# 06_MIPI_CSI_Camera.net
KiCad netlist of a schematic drawn in Altium Designer
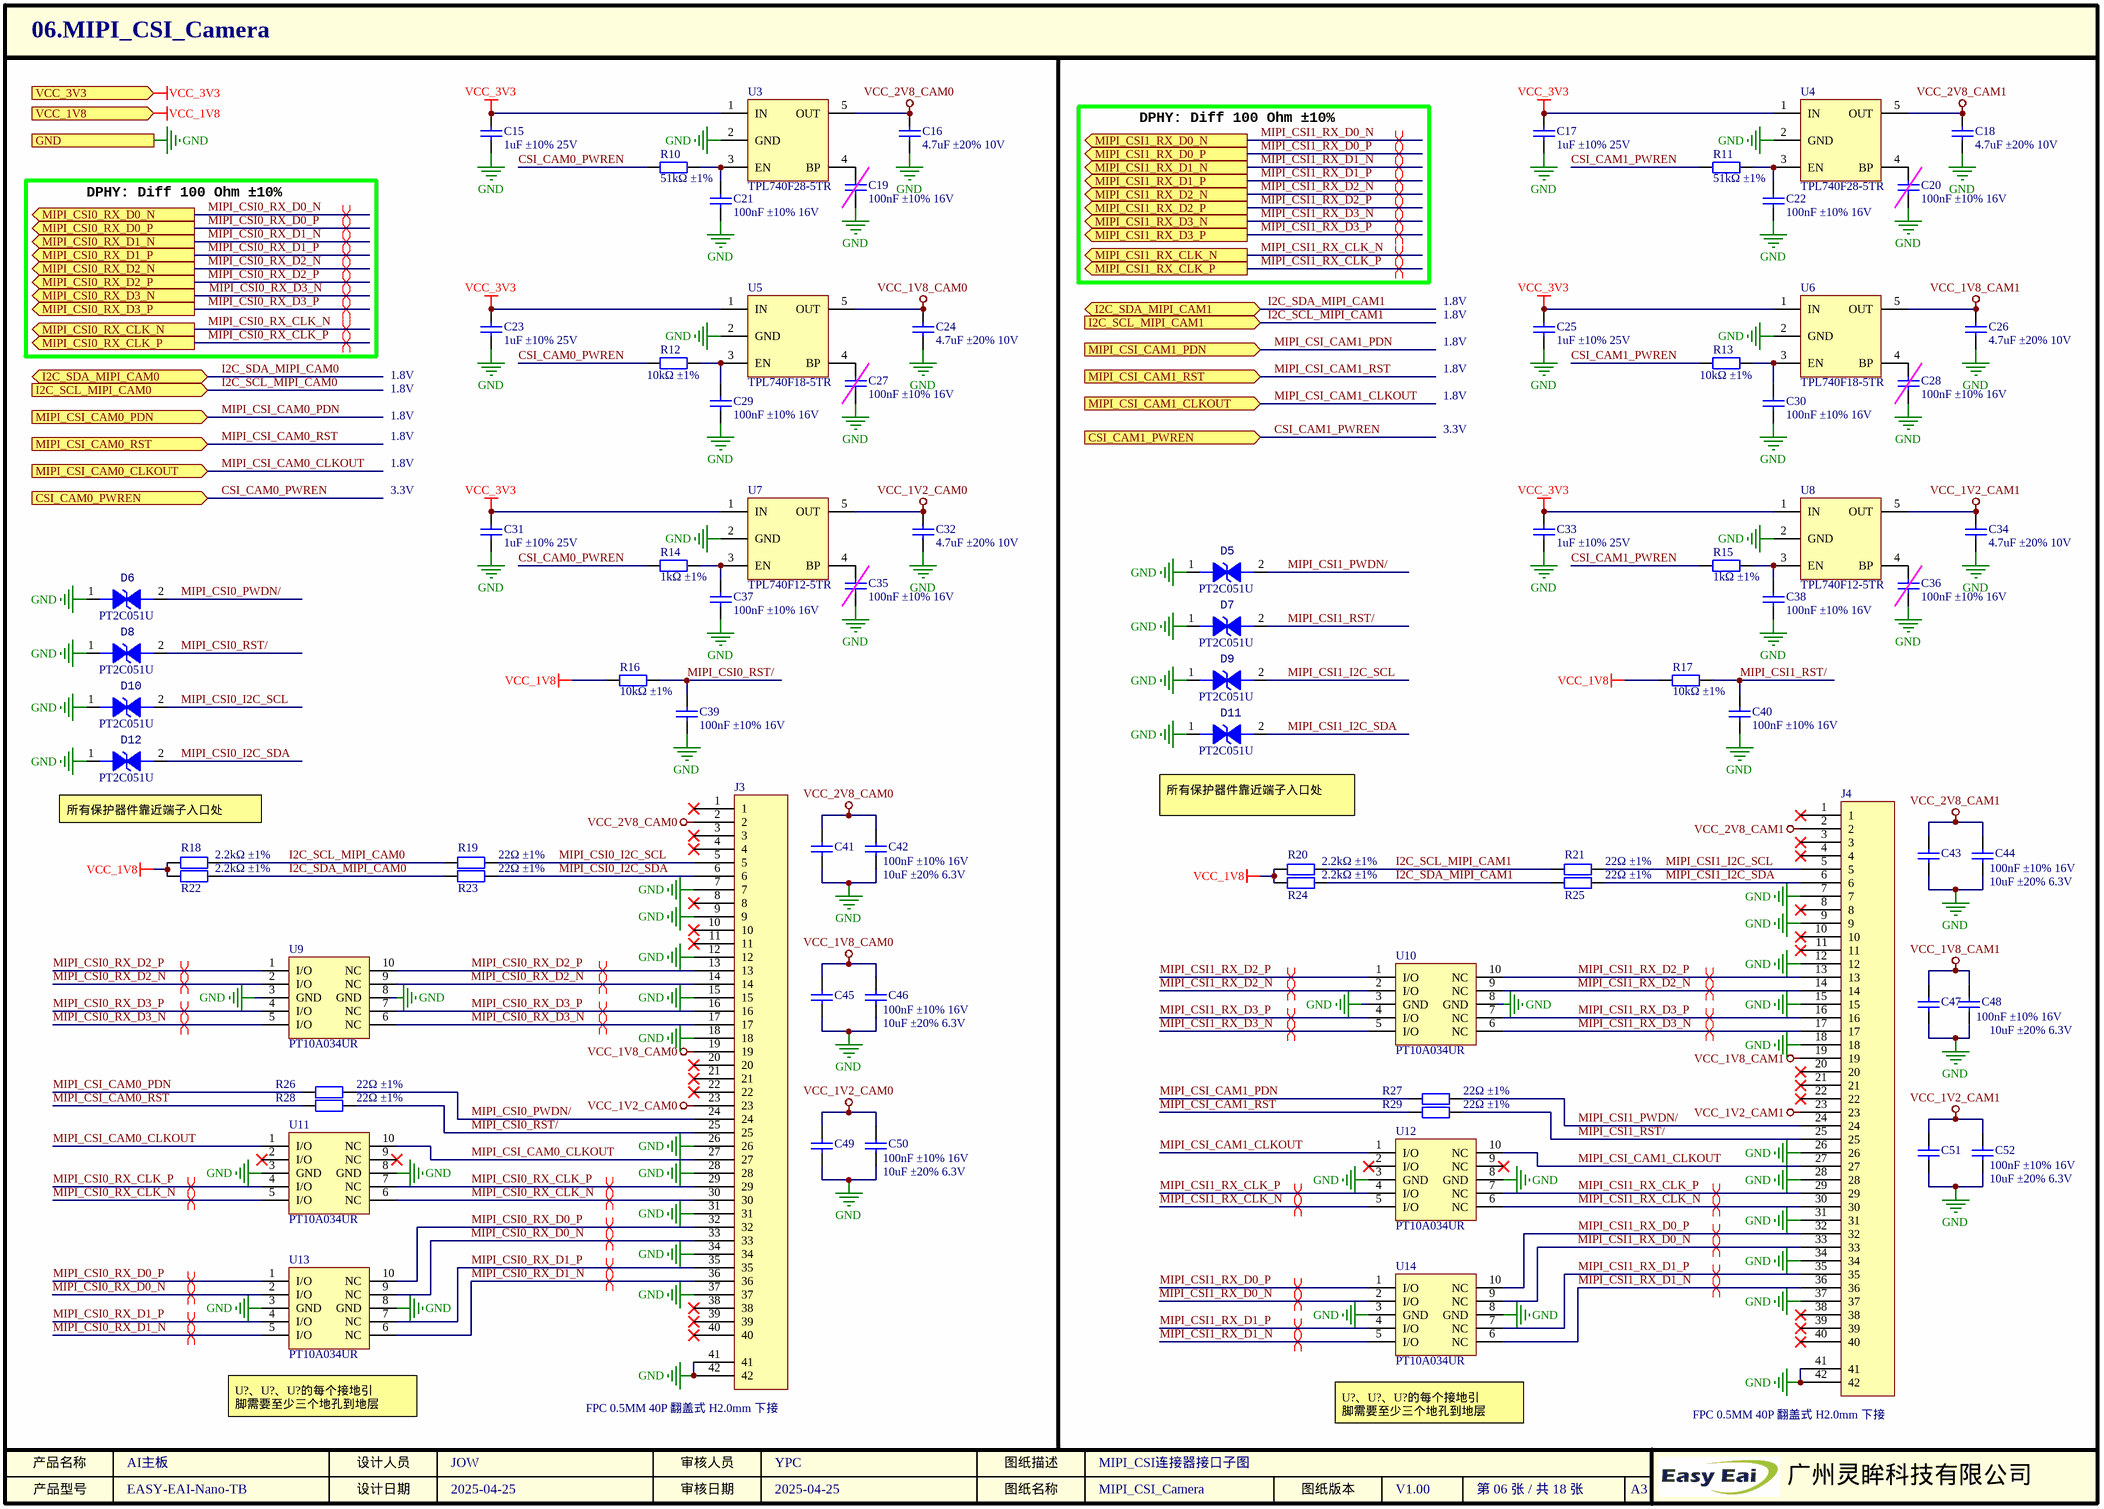
[diagram p0: 06.MIPI_CSI_Camera.SchDoc]

(export (version "E")
  (design (tool "Eeschema 10.0.6"))
  (components
    (comp (ref "C15")
      (value "CL05A105KA5NQNC")
      (footprint "0402_C")
      (description "SPZL000337")
      (fields (field (name "描述") "1uF ±10% 25V"))
      (libsource (lib "altium-import") (part "root_1_0402 1uF ±10% 25V_"))
    )
    (comp (ref "C16")
      (value "CL05A475MP5NRNC")
      (footprint "0402_C")
      (description "SPZL000339")
      (fields (field (name "描述") "4.7uF ±20% 10V"))
      (libsource (lib "altium-import") (part "root_1_0402 4.7uF ±20% 10V_"))
    )
    (comp (ref "C17")
      (value "CL05A105KA5NQNC")
      (footprint "0402_C")
      (description "SPZL000337")
      (fields (field (name "描述") "1uF ±10% 25V"))
      (libsource (lib "altium-import") (part "root_1_0402 1uF ±10% 25V_"))
    )
    (comp (ref "C18")
      (value "CL05A475MP5NRNC")
      (footprint "0402_C")
      (description "SPZL000339")
      (fields (field (name "描述") "4.7uF ±20% 10V"))
      (libsource (lib "altium-import") (part "root_1_0402 4.7uF ±20% 10V_"))
    )
    (comp (ref "C19")
      (value "CL05B104KO5NNNC")
      (footprint "0402_C")
      (description "SPZL000259")
      (fields (field (name "描述") "100nF ±10% 16V"))
      (libsource (lib "altium-import") (part "root_1_0402 100nF ±10% 16V_"))
    )
    (comp (ref "C20")
      (value "CL05B104KO5NNNC")
      (footprint "0402_C")
      (description "SPZL000259")
      (fields (field (name "描述") "100nF ±10% 16V"))
      (libsource (lib "altium-import") (part "root_1_0402 100nF ±10% 16V_"))
    )
    (comp (ref "C21")
      (value "CL05B104KO5NNNC")
      (footprint "0402_C")
      (description "SPZL000259")
      (fields (field (name "描述") "100nF ±10% 16V"))
      (libsource (lib "altium-import") (part "root_1_0402 100nF ±10% 16V_"))
    )
    (comp (ref "C22")
      (value "CL05B104KO5NNNC")
      (footprint "0402_C")
      (description "SPZL000259")
      (fields (field (name "描述") "100nF ±10% 16V"))
      (libsource (lib "altium-import") (part "root_1_0402 100nF ±10% 16V_"))
    )
    (comp (ref "C23")
      (value "CL05A105KA5NQNC")
      (footprint "0402_C")
      (description "SPZL000337")
      (fields (field (name "描述") "1uF ±10% 25V"))
      (libsource (lib "altium-import") (part "root_1_0402 1uF ±10% 25V_"))
    )
    (comp (ref "C24")
      (value "CL05A475MP5NRNC")
      (footprint "0402_C")
      (description "SPZL000339")
      (fields (field (name "描述") "4.7uF ±20% 10V"))
      (libsource (lib "altium-import") (part "root_1_0402 4.7uF ±20% 10V_"))
    )
    (comp (ref "C25")
      (value "CL05A105KA5NQNC")
      (footprint "0402_C")
      (description "SPZL000337")
      (fields (field (name "描述") "1uF ±10% 25V"))
      (libsource (lib "altium-import") (part "root_1_0402 1uF ±10% 25V_"))
    )
    (comp (ref "C26")
      (value "CL05A475MP5NRNC")
      (footprint "0402_C")
      (description "SPZL000339")
      (fields (field (name "描述") "4.7uF ±20% 10V"))
      (libsource (lib "altium-import") (part "root_1_0402 4.7uF ±20% 10V_"))
    )
    (comp (ref "C27")
      (value "CL05B104KO5NNNC")
      (footprint "0402_C")
      (description "SPZL000259")
      (fields (field (name "描述") "100nF ±10% 16V"))
      (libsource (lib "altium-import") (part "root_1_0402 100nF ±10% 16V_"))
    )
    (comp (ref "C28")
      (value "CL05B104KO5NNNC")
      (footprint "0402_C")
      (description "SPZL000259")
      (fields (field (name "描述") "100nF ±10% 16V"))
      (libsource (lib "altium-import") (part "root_1_0402 100nF ±10% 16V_"))
    )
    (comp (ref "C29")
      (value "CL05B104KO5NNNC")
      (footprint "0402_C")
      (description "SPZL000259")
      (fields (field (name "描述") "100nF ±10% 16V"))
      (libsource (lib "altium-import") (part "root_1_0402 100nF ±10% 16V_"))
    )
    (comp (ref "C30")
      (value "CL05B104KO5NNNC")
      (footprint "0402_C")
      (description "SPZL000259")
      (fields (field (name "描述") "100nF ±10% 16V"))
      (libsource (lib "altium-import") (part "root_1_0402 100nF ±10% 16V_"))
    )
    (comp (ref "C31")
      (value "CL05A105KA5NQNC")
      (footprint "0402_C")
      (description "SPZL000337")
      (fields (field (name "描述") "1uF ±10% 25V"))
      (libsource (lib "altium-import") (part "root_1_0402 1uF ±10% 25V_"))
    )
    (comp (ref "C32")
      (value "CL05A475MP5NRNC")
      (footprint "0402_C")
      (description "SPZL000339")
      (fields (field (name "描述") "4.7uF ±20% 10V"))
      (libsource (lib "altium-import") (part "root_1_0402 4.7uF ±20% 10V_"))
    )
    (comp (ref "C33")
      (value "CL05A105KA5NQNC")
      (footprint "0402_C")
      (description "SPZL000337")
      (fields (field (name "描述") "1uF ±10% 25V"))
      (libsource (lib "altium-import") (part "root_1_0402 1uF ±10% 25V_"))
    )
    (comp (ref "C34")
      (value "CL05A475MP5NRNC")
      (footprint "0402_C")
      (description "SPZL000339")
      (fields (field (name "描述") "4.7uF ±20% 10V"))
      (libsource (lib "altium-import") (part "root_1_0402 4.7uF ±20% 10V_"))
    )
    (comp (ref "C35")
      (value "CL05B104KO5NNNC")
      (footprint "0402_C")
      (description "SPZL000259")
      (fields (field (name "描述") "100nF ±10% 16V"))
      (libsource (lib "altium-import") (part "root_1_0402 100nF ±10% 16V_"))
    )
    (comp (ref "C36")
      (value "CL05B104KO5NNNC")
      (footprint "0402_C")
      (description "SPZL000259")
      (fields (field (name "描述") "100nF ±10% 16V"))
      (libsource (lib "altium-import") (part "root_1_0402 100nF ±10% 16V_"))
    )
    (comp (ref "C37")
      (value "CL05B104KO5NNNC")
      (footprint "0402_C")
      (description "SPZL000259")
      (fields (field (name "描述") "100nF ±10% 16V"))
      (libsource (lib "altium-import") (part "root_1_0402 100nF ±10% 16V_"))
    )
    (comp (ref "C38")
      (value "CL05B104KO5NNNC")
      (footprint "0402_C")
      (description "SPZL000259")
      (fields (field (name "描述") "100nF ±10% 16V"))
      (libsource (lib "altium-import") (part "root_1_0402 100nF ±10% 16V_"))
    )
    (comp (ref "C39")
      (value "CL05B104KO5NNNC")
      (footprint "0402_C")
      (description "SPZL000259")
      (fields (field (name "描述") "100nF ±10% 16V"))
      (libsource (lib "altium-import") (part "root_1_0402 100nF ±10% 16V_"))
    )
    (comp (ref "C40")
      (value "CL05B104KO5NNNC")
      (footprint "0402_C")
      (description "SPZL000259")
      (fields (field (name "描述") "100nF ±10% 16V"))
      (libsource (lib "altium-import") (part "root_1_0402 100nF ±10% 16V_"))
    )
    (comp (ref "C41")
      (value "CL05A106MQ5NUNC")
      (footprint "0402_C")
      (description "SPZL000269")
      (fields (field (name "描述") "10uF ±20% 6.3V"))
      (libsource (lib "altium-import") (part "root_1_0402 10uF ±20% 6.3V_"))
    )
    (comp (ref "C42")
      (value "CL05B104KO5NNNC")
      (footprint "0402_C")
      (description "SPZL000259")
      (fields (field (name "描述") "100nF ±10% 16V"))
      (libsource (lib "altium-import") (part "root_1_0402 100nF ±10% 16V_"))
    )
    (comp (ref "C43")
      (value "CL05A106MQ5NUNC")
      (footprint "0402_C")
      (description "SPZL000269")
      (fields (field (name "描述") "10uF ±20% 6.3V"))
      (libsource (lib "altium-import") (part "root_1_0402 10uF ±20% 6.3V_"))
    )
    (comp (ref "C44")
      (value "CL05B104KO5NNNC")
      (footprint "0402_C")
      (description "SPZL000259")
      (fields (field (name "描述") "100nF ±10% 16V"))
      (libsource (lib "altium-import") (part "root_1_0402 100nF ±10% 16V_"))
    )
    (comp (ref "C45")
      (value "CL05A106MQ5NUNC")
      (footprint "0402_C")
      (description "SPZL000269")
      (fields (field (name "描述") "10uF ±20% 6.3V"))
      (libsource (lib "altium-import") (part "root_1_0402 10uF ±20% 6.3V_"))
    )
    (comp (ref "C46")
      (value "CL05B104KO5NNNC")
      (footprint "0402_C")
      (description "SPZL000259")
      (fields (field (name "描述") "100nF ±10% 16V"))
      (libsource (lib "altium-import") (part "root_1_0402 100nF ±10% 16V_"))
    )
    (comp (ref "C47")
      (value "CL05A106MQ5NUNC")
      (footprint "0402_C")
      (description "SPZL000269")
      (fields (field (name "描述") "10uF ±20% 6.3V"))
      (libsource (lib "altium-import") (part "root_1_0402 10uF ±20% 6.3V_"))
    )
    (comp (ref "C48")
      (value "CL05B104KO5NNNC")
      (footprint "0402_C")
      (description "SPZL000259")
      (fields (field (name "描述") "100nF ±10% 16V"))
      (libsource (lib "altium-import") (part "root_1_0402 100nF ±10% 16V_"))
    )
    (comp (ref "C49")
      (value "CL05A106MQ5NUNC")
      (footprint "0402_C")
      (description "SPZL000269")
      (fields (field (name "描述") "10uF ±20% 6.3V"))
      (libsource (lib "altium-import") (part "root_1_0402 10uF ±20% 6.3V_"))
    )
    (comp (ref "C50")
      (value "CL05B104KO5NNNC")
      (footprint "0402_C")
      (description "SPZL000259")
      (fields (field (name "描述") "100nF ±10% 16V"))
      (libsource (lib "altium-import") (part "root_1_0402 100nF ±10% 16V_"))
    )
    (comp (ref "C51")
      (value "CL05A106MQ5NUNC")
      (footprint "0402_C")
      (description "SPZL000269")
      (fields (field (name "描述") "10uF ±20% 6.3V"))
      (libsource (lib "altium-import") (part "root_1_0402 10uF ±20% 6.3V_"))
    )
    (comp (ref "C52")
      (value "CL05B104KO5NNNC")
      (footprint "0402_C")
      (description "SPZL000259")
      (fields (field (name "描述") "100nF ±10% 16V"))
      (libsource (lib "altium-import") (part "root_1_0402 100nF ±10% 16V_"))
    )
    (comp (ref "D5")
      (value "PT2C051U")
      (footprint "DFN1006")
      (description "SPZL001147")
      (fields (field (name "型号") "PT2C051U"))
      (libsource (lib "ESD_EASY-EAI") (part "PT2C051U"))
    )
    (comp (ref "D6")
      (value "PT2C051U")
      (footprint "DFN1006")
      (description "SPZL001147")
      (fields (field (name "型号") "PT2C051U"))
      (libsource (lib "ESD_EASY-EAI") (part "PT2C051U"))
    )
    (comp (ref "D7")
      (value "PT2C051U")
      (footprint "DFN1006")
      (description "SPZL001147")
      (fields (field (name "型号") "PT2C051U"))
      (libsource (lib "ESD_EASY-EAI") (part "PT2C051U"))
    )
    (comp (ref "D8")
      (value "PT2C051U")
      (footprint "DFN1006")
      (description "SPZL001147")
      (fields (field (name "型号") "PT2C051U"))
      (libsource (lib "ESD_EASY-EAI") (part "PT2C051U"))
    )
    (comp (ref "D9")
      (value "PT2C051U")
      (footprint "DFN1006")
      (description "SPZL001147")
      (fields (field (name "型号") "PT2C051U"))
      (libsource (lib "ESD_EASY-EAI") (part "PT2C051U"))
    )
    (comp (ref "D10")
      (value "PT2C051U")
      (footprint "DFN1006")
      (description "SPZL001147")
      (fields (field (name "型号") "PT2C051U"))
      (libsource (lib "ESD_EASY-EAI") (part "PT2C051U"))
    )
    (comp (ref "D11")
      (value "PT2C051U")
      (footprint "DFN1006")
      (description "SPZL001147")
      (fields (field (name "型号") "PT2C051U"))
      (libsource (lib "ESD_EASY-EAI") (part "PT2C051U"))
    )
    (comp (ref "D12")
      (value "PT2C051U")
      (footprint "DFN1006")
      (description "SPZL001147")
      (fields (field (name "型号") "PT2C051U"))
      (libsource (lib "ESD_EASY-EAI") (part "PT2C051U"))
    )
    (comp (ref "J3")
      (value "AFC01-S40FCA-00")
      (footprint "FFC0.5-40P")
      (description "SPZL000107")
      (fields (field (name "描述") "FPC 0.5MM 40P 翻盖式 H2.0mm 下接"))
      (libsource (lib "FPC_EASY-EAI") (part "FPC 0.5MM 40P 翻盖式 H2.0mm 下接"))
    )
    (comp (ref "J4")
      (value "AFC01-S40FCA-00")
      (footprint "FFC0.5-40P")
      (description "SPZL000107")
      (fields (field (name "描述") "FPC 0.5MM 40P 翻盖式 H2.0mm 下接"))
      (libsource (lib "FPC_EASY-EAI") (part "FPC 0.5MM 40P 翻盖式 H2.0mm 下接"))
    )
    (comp (ref "R10")
      (value "0402WGF5102TCE")
      (footprint "0402_R")
      (description "SPZL000788")
      (fields (field (name "描述") "51kΩ ±1%"))
      (libsource (lib "RES_EASY-EAI") (part "0402 51kΩ ±1%"))
    )
    (comp (ref "R11")
      (value "0402WGF5102TCE")
      (footprint "0402_R")
      (description "SPZL000788")
      (fields (field (name "描述") "51kΩ ±1%"))
      (libsource (lib "RES_EASY-EAI") (part "0402 51kΩ ±1%"))
    )
    (comp (ref "R12")
      (value "0402WGF1002TCE")
      (footprint "0402_R")
      (description "SPZL000271")
      (fields (field (name "描述") "10kΩ ±1%"))
      (libsource (lib "altium-import") (part "root_0_0402 10kΩ ±1%_"))
    )
    (comp (ref "R13")
      (value "0402WGF1002TCE")
      (footprint "0402_R")
      (description "SPZL000271")
      (fields (field (name "描述") "10kΩ ±1%"))
      (libsource (lib "altium-import") (part "root_0_0402 10kΩ ±1%_"))
    )
    (comp (ref "R14")
      (value "0402WGF1001TCE")
      (footprint "0402_R")
      (description "SPZL000275")
      (fields (field (name "描述") "1kΩ ±1%"))
      (libsource (lib "RES_EASY-EAI") (part "0402 1kΩ ±1%"))
    )
    (comp (ref "R15")
      (value "0402WGF1001TCE")
      (footprint "0402_R")
      (description "SPZL000275")
      (fields (field (name "描述") "1kΩ ±1%"))
      (libsource (lib "RES_EASY-EAI") (part "0402 1kΩ ±1%"))
    )
    (comp (ref "R16")
      (value "0402WGF1002TCE")
      (footprint "0402_R")
      (description "SPZL000271")
      (fields (field (name "描述") "10kΩ ±1%"))
      (libsource (lib "altium-import") (part "root_2_0402 10kΩ ±1%_"))
    )
    (comp (ref "R17")
      (value "0402WGF1002TCE")
      (footprint "0402_R")
      (description "SPZL000271")
      (fields (field (name "描述") "10kΩ ±1%"))
      (libsource (lib "altium-import") (part "root_2_0402 10kΩ ±1%_"))
    )
    (comp (ref "R18")
      (value "AC0402FR-072K2L")
      (footprint "0402_R")
      (description "SPZL000307")
      (fields (field (name "描述") "2.2kΩ ±1%"))
      (libsource (lib "RES_EASY-EAI") (part "0402 2.2kΩ ±1%"))
    )
    (comp (ref "R19")
      (value "0402WGF220JTCE")
      (footprint "0402_R")
      (description "SPZL000279")
      (fields (field (name "描述") "22Ω ±1%"))
      (libsource (lib "altium-import") (part "root_0_0402 22Ω ±1%_"))
    )
    (comp (ref "R20")
      (value "AC0402FR-072K2L")
      (footprint "0402_R")
      (description "SPZL000307")
      (fields (field (name "描述") "2.2kΩ ±1%"))
      (libsource (lib "RES_EASY-EAI") (part "0402 2.2kΩ ±1%"))
    )
    (comp (ref "R21")
      (value "0402WGF220JTCE")
      (footprint "0402_R")
      (description "SPZL000279")
      (fields (field (name "描述") "22Ω ±1%"))
      (libsource (lib "altium-import") (part "root_0_0402 22Ω ±1%_"))
    )
    (comp (ref "R22")
      (value "AC0402FR-072K2L")
      (footprint "0402_R")
      (description "SPZL000307")
      (fields (field (name "描述") "2.2kΩ ±1%"))
      (libsource (lib "RES_EASY-EAI") (part "0402 2.2kΩ ±1%"))
    )
    (comp (ref "R23")
      (value "0402WGF220JTCE")
      (footprint "0402_R")
      (description "SPZL000279")
      (fields (field (name "描述") "22Ω ±1%"))
      (libsource (lib "altium-import") (part "root_0_0402 22Ω ±1%_"))
    )
    (comp (ref "R24")
      (value "AC0402FR-072K2L")
      (footprint "0402_R")
      (description "SPZL000307")
      (fields (field (name "描述") "2.2kΩ ±1%"))
      (libsource (lib "RES_EASY-EAI") (part "0402 2.2kΩ ±1%"))
    )
    (comp (ref "R25")
      (value "0402WGF220JTCE")
      (footprint "0402_R")
      (description "SPZL000279")
      (fields (field (name "描述") "22Ω ±1%"))
      (libsource (lib "altium-import") (part "root_0_0402 22Ω ±1%_"))
    )
    (comp (ref "R26")
      (value "0402WGF220JTCE")
      (footprint "0402_R")
      (description "SPZL000279")
      (fields (field (name "描述") "22Ω ±1%"))
      (libsource (lib "altium-import") (part "root_0_0402 22Ω ±1%_"))
    )
    (comp (ref "R27")
      (value "0402WGF220JTCE")
      (footprint "0402_R")
      (description "SPZL000279")
      (fields (field (name "描述") "22Ω ±1%"))
      (libsource (lib "altium-import") (part "root_0_0402 22Ω ±1%_"))
    )
    (comp (ref "R28")
      (value "0402WGF220JTCE")
      (footprint "0402_R")
      (description "SPZL000279")
      (fields (field (name "描述") "22Ω ±1%"))
      (libsource (lib "altium-import") (part "root_0_0402 22Ω ±1%_"))
    )
    (comp (ref "R29")
      (value "0402WGF220JTCE")
      (footprint "0402_R")
      (description "SPZL000279")
      (fields (field (name "描述") "22Ω ±1%"))
      (libsource (lib "altium-import") (part "root_0_0402 22Ω ±1%_"))
    )
    (comp (ref "U3")
      (value "TPL740F28-5TR")
      (footprint "SOT-23-5")
      (description "SPZL000631")
      (fields (field (name "型号") "TPL740F28-5TR"))
      (libsource (lib "EASY-EAI-Nano-TB V1.01") (part "TPL740F28-5TR"))
    )
    (comp (ref "U4")
      (value "TPL740F28-5TR")
      (footprint "SOT-23-5")
      (description "SPZL000631")
      (fields (field (name "型号") "TPL740F28-5TR"))
      (libsource (lib "EASY-EAI-Nano-TB V1.01") (part "TPL740F28-5TR"))
    )
    (comp (ref "U5")
      (value "TPL740F18-5TR")
      (footprint "SOT-23-5")
      (description "SPZL000630")
      (fields (field (name "型号") "TPL740F18-5TR"))
      (libsource (lib "EASY-EAI-Nano-TB V1.01") (part "TPL740F18-5TR"))
    )
    (comp (ref "U6")
      (value "TPL740F18-5TR")
      (footprint "SOT-23-5")
      (description "SPZL000630")
      (fields (field (name "型号") "TPL740F18-5TR"))
      (libsource (lib "EASY-EAI-Nano-TB V1.01") (part "TPL740F18-5TR"))
    )
    (comp (ref "U7")
      (value "TPL740F12-5TR")
      (footprint "SOT-23-5")
      (description "SPZL000632")
      (fields (field (name "型号") "TPL740F12-5TR"))
      (libsource (lib "EASY-EAI-Nano-TB V1.01") (part "TPL740F12-5TR"))
    )
    (comp (ref "U8")
      (value "TPL740F12-5TR")
      (footprint "SOT-23-5")
      (description "SPZL000632")
      (fields (field (name "型号") "TPL740F12-5TR"))
      (libsource (lib "EASY-EAI-Nano-TB V1.01") (part "TPL740F12-5TR"))
    )
    (comp (ref "U9")
      (value "PT10A034UR")
      (footprint "DFN2510")
      (description "SPZL001146")
      (fields (field (name "型号") "PT10A034UR"))
      (libsource (lib "ESD_EASY-EAI") (part "PT10A034UR"))
    )
    (comp (ref "U10")
      (value "PT10A034UR")
      (footprint "DFN2510")
      (description "SPZL001146")
      (fields (field (name "型号") "PT10A034UR"))
      (libsource (lib "ESD_EASY-EAI") (part "PT10A034UR"))
    )
    (comp (ref "U11")
      (value "PT10A034UR")
      (footprint "DFN2510")
      (description "SPZL001146")
      (fields (field (name "型号") "PT10A034UR"))
      (libsource (lib "ESD_EASY-EAI") (part "PT10A034UR"))
    )
    (comp (ref "U12")
      (value "PT10A034UR")
      (footprint "DFN2510")
      (description "SPZL001146")
      (fields (field (name "型号") "PT10A034UR"))
      (libsource (lib "ESD_EASY-EAI") (part "PT10A034UR"))
    )
    (comp (ref "U13")
      (value "PT10A034UR")
      (footprint "DFN2510")
      (description "SPZL001146")
      (fields (field (name "型号") "PT10A034UR"))
      (libsource (lib "ESD_EASY-EAI") (part "PT10A034UR"))
    )
    (comp (ref "U14")
      (value "PT10A034UR")
      (footprint "DFN2510")
      (description "SPZL001146")
      (fields (field (name "型号") "PT10A034UR"))
      (libsource (lib "ESD_EASY-EAI") (part "PT10A034UR"))
    )
  )
  (nets
    (net (code "1") (name "/CSI_CAM0_PWREN") (class "Default")
      (node (ref "R10") (pin "1") (pinfunction "1_1") (pintype "passive"))
      (node (ref "R12") (pin "1") (pinfunction "1_1") (pintype "passive"))
      (node (ref "R14") (pin "1") (pinfunction "1_1") (pintype "passive"))
    )
    (net (code "2") (name "/CSI_CAM1_PWREN") (class "Default")
      (node (ref "R11") (pin "1") (pinfunction "1_1") (pintype "passive"))
      (node (ref "R13") (pin "1") (pinfunction "1_1") (pintype "passive"))
      (node (ref "R15") (pin "1") (pinfunction "1_1") (pintype "passive"))
    )
    (net (code "3") (name "/I2C_SCL_MIPI_CAM0") (class "Default")
      (node (ref "R18") (pin "2") (pinfunction "2_2") (pintype "passive"))
      (node (ref "R19") (pin "1") (pinfunction "1_1") (pintype "passive"))
    )
    (net (code "4") (name "/I2C_SCL_MIPI_CAM1") (class "Default")
      (node (ref "R20") (pin "2") (pinfunction "2_2") (pintype "passive"))
      (node (ref "R21") (pin "1") (pinfunction "1_1") (pintype "passive"))
    )
    (net (code "5") (name "/I2C_SDA_MIPI_CAM0") (class "Default")
      (node (ref "R22") (pin "2") (pinfunction "2_2") (pintype "passive"))
      (node (ref "R23") (pin "1") (pinfunction "1_1") (pintype "passive"))
    )
    (net (code "6") (name "/I2C_SDA_MIPI_CAM1") (class "Default")
      (node (ref "R24") (pin "2") (pinfunction "2_2") (pintype "passive"))
      (node (ref "R25") (pin "1") (pinfunction "1_1") (pintype "passive"))
    )
    (net (code "7") (name "/MIPI_CSI0_I2C_SCL") (class "Default")
      (node (ref "D10") (pin "2") (pinfunction "2_2") (pintype "passive"))
      (node (ref "J3") (pin "5") (pinfunction "5_5") (pintype "passive"))
      (node (ref "R19") (pin "2") (pinfunction "2_2") (pintype "passive"))
    )
    (net (code "8") (name "/MIPI_CSI0_I2C_SDA") (class "Default")
      (node (ref "D12") (pin "2") (pinfunction "2_2") (pintype "passive"))
      (node (ref "J3") (pin "6") (pinfunction "6_6") (pintype "passive"))
      (node (ref "R23") (pin "2") (pinfunction "2_2") (pintype "passive"))
    )
    (net (code "9") (name "/MIPI_CSI0_PWDN{slash}") (class "Default")
      (node (ref "D6") (pin "2") (pinfunction "2_2") (pintype "passive"))
      (node (ref "J3") (pin "24") (pinfunction "24_24") (pintype "passive"))
      (node (ref "R26") (pin "2") (pinfunction "2_2") (pintype "passive"))
    )
    (net (code "10") (name "/MIPI_CSI0_RST{slash}") (class "Default")
      (node (ref "C39") (pin "2") (pinfunction "2_2") (pintype "passive"))
      (node (ref "D8") (pin "2") (pinfunction "2_2") (pintype "passive"))
      (node (ref "J3") (pin "25") (pinfunction "25_25") (pintype "passive"))
      (node (ref "R16") (pin "1") (pinfunction "1_1") (pintype "passive"))
      (node (ref "R28") (pin "2") (pinfunction "2_2") (pintype "passive"))
    )
    (net (code "11") (name "/MIPI_CSI0_RX_CLK_N") (class "Default")
      (node (ref "J3") (pin "30") (pinfunction "30_30") (pintype "passive"))
      (node (ref "U11") (pin "5") (pinfunction "I/O_5") (pintype "passive"))
      (node (ref "U11") (pin "6") (pinfunction "NC_6") (pintype "passive"))
    )
    (net (code "12") (name "/MIPI_CSI0_RX_CLK_P") (class "Default")
      (node (ref "J3") (pin "29") (pinfunction "29_29") (pintype "passive"))
      (node (ref "U11") (pin "4") (pinfunction "I/O_4") (pintype "passive"))
      (node (ref "U11") (pin "7") (pinfunction "NC_7") (pintype "passive"))
    )
    (net (code "13") (name "/MIPI_CSI0_RX_D0_N") (class "Default")
      (node (ref "J3") (pin "33") (pinfunction "33_33") (pintype "passive"))
      (node (ref "U13") (pin "2") (pinfunction "I/O_2") (pintype "passive"))
      (node (ref "U13") (pin "9") (pinfunction "NC_9") (pintype "passive"))
    )
    (net (code "14") (name "/MIPI_CSI0_RX_D0_P") (class "Default")
      (node (ref "J3") (pin "32") (pinfunction "32_32") (pintype "passive"))
      (node (ref "U13") (pin "1") (pinfunction "I/O_1") (pintype "passive"))
      (node (ref "U13") (pin "10") (pinfunction "NC_10") (pintype "passive"))
    )
    (net (code "15") (name "/MIPI_CSI0_RX_D1_N") (class "Default")
      (node (ref "J3") (pin "36") (pinfunction "36_36") (pintype "passive"))
      (node (ref "U13") (pin "5") (pinfunction "I/O_5") (pintype "passive"))
      (node (ref "U13") (pin "6") (pinfunction "NC_6") (pintype "passive"))
    )
    (net (code "16") (name "/MIPI_CSI0_RX_D1_P") (class "Default")
      (node (ref "J3") (pin "35") (pinfunction "35_35") (pintype "passive"))
      (node (ref "U13") (pin "4") (pinfunction "I/O_4") (pintype "passive"))
      (node (ref "U13") (pin "7") (pinfunction "NC_7") (pintype "passive"))
    )
    (net (code "17") (name "/MIPI_CSI0_RX_D2_N") (class "Default")
      (node (ref "J3") (pin "14") (pinfunction "14_14") (pintype "passive"))
      (node (ref "U9") (pin "2") (pinfunction "I/O_2") (pintype "passive"))
      (node (ref "U9") (pin "9") (pinfunction "NC_9") (pintype "passive"))
    )
    (net (code "18") (name "/MIPI_CSI0_RX_D2_P") (class "Default")
      (node (ref "J3") (pin "13") (pinfunction "13_13") (pintype "passive"))
      (node (ref "U9") (pin "1") (pinfunction "I/O_1") (pintype "passive"))
      (node (ref "U9") (pin "10") (pinfunction "NC_10") (pintype "passive"))
    )
    (net (code "19") (name "/MIPI_CSI0_RX_D3_N") (class "Default")
      (node (ref "J3") (pin "17") (pinfunction "17_17") (pintype "passive"))
      (node (ref "U9") (pin "5") (pinfunction "I/O_5") (pintype "passive"))
      (node (ref "U9") (pin "6") (pinfunction "NC_6") (pintype "passive"))
    )
    (net (code "20") (name "/MIPI_CSI0_RX_D3_P") (class "Default")
      (node (ref "J3") (pin "16") (pinfunction "16_16") (pintype "passive"))
      (node (ref "U9") (pin "4") (pinfunction "I/O_4") (pintype "passive"))
      (node (ref "U9") (pin "7") (pinfunction "NC_7") (pintype "passive"))
    )
    (net (code "21") (name "/MIPI_CSI1_I2C_SCL") (class "Default")
      (node (ref "D9") (pin "2") (pinfunction "2_2") (pintype "passive"))
      (node (ref "J4") (pin "5") (pinfunction "5_5") (pintype "passive"))
      (node (ref "R21") (pin "2") (pinfunction "2_2") (pintype "passive"))
    )
    (net (code "22") (name "/MIPI_CSI1_I2C_SDA") (class "Default")
      (node (ref "D11") (pin "2") (pinfunction "2_2") (pintype "passive"))
      (node (ref "J4") (pin "6") (pinfunction "6_6") (pintype "passive"))
      (node (ref "R25") (pin "2") (pinfunction "2_2") (pintype "passive"))
    )
    (net (code "23") (name "/MIPI_CSI1_PWDN{slash}") (class "Default")
      (node (ref "D5") (pin "2") (pinfunction "2_2") (pintype "passive"))
      (node (ref "J4") (pin "24") (pinfunction "24_24") (pintype "passive"))
      (node (ref "R27") (pin "2") (pinfunction "2_2") (pintype "passive"))
    )
    (net (code "24") (name "/MIPI_CSI1_RST{slash}") (class "Default")
      (node (ref "C40") (pin "2") (pinfunction "2_2") (pintype "passive"))
      (node (ref "D7") (pin "2") (pinfunction "2_2") (pintype "passive"))
      (node (ref "J4") (pin "25") (pinfunction "25_25") (pintype "passive"))
      (node (ref "R17") (pin "1") (pinfunction "1_1") (pintype "passive"))
      (node (ref "R29") (pin "2") (pinfunction "2_2") (pintype "passive"))
    )
    (net (code "25") (name "/MIPI_CSI1_RX_CLK_N") (class "Default")
      (node (ref "J4") (pin "30") (pinfunction "30_30") (pintype "passive"))
      (node (ref "U12") (pin "5") (pinfunction "I/O_5") (pintype "passive"))
      (node (ref "U12") (pin "6") (pinfunction "NC_6") (pintype "passive"))
    )
    (net (code "26") (name "/MIPI_CSI1_RX_CLK_P") (class "Default")
      (node (ref "J4") (pin "29") (pinfunction "29_29") (pintype "passive"))
      (node (ref "U12") (pin "4") (pinfunction "I/O_4") (pintype "passive"))
      (node (ref "U12") (pin "7") (pinfunction "NC_7") (pintype "passive"))
    )
    (net (code "27") (name "/MIPI_CSI1_RX_D0_N") (class "Default")
      (node (ref "J4") (pin "33") (pinfunction "33_33") (pintype "passive"))
      (node (ref "U14") (pin "2") (pinfunction "I/O_2") (pintype "passive"))
      (node (ref "U14") (pin "9") (pinfunction "NC_9") (pintype "passive"))
    )
    (net (code "28") (name "/MIPI_CSI1_RX_D0_P") (class "Default")
      (node (ref "J4") (pin "32") (pinfunction "32_32") (pintype "passive"))
      (node (ref "U14") (pin "1") (pinfunction "I/O_1") (pintype "passive"))
      (node (ref "U14") (pin "10") (pinfunction "NC_10") (pintype "passive"))
    )
    (net (code "29") (name "/MIPI_CSI1_RX_D1_N") (class "Default")
      (node (ref "J4") (pin "36") (pinfunction "36_36") (pintype "passive"))
      (node (ref "U14") (pin "5") (pinfunction "I/O_5") (pintype "passive"))
      (node (ref "U14") (pin "6") (pinfunction "NC_6") (pintype "passive"))
    )
    (net (code "30") (name "/MIPI_CSI1_RX_D1_P") (class "Default")
      (node (ref "J4") (pin "35") (pinfunction "35_35") (pintype "passive"))
      (node (ref "U14") (pin "4") (pinfunction "I/O_4") (pintype "passive"))
      (node (ref "U14") (pin "7") (pinfunction "NC_7") (pintype "passive"))
    )
    (net (code "31") (name "/MIPI_CSI1_RX_D2_N") (class "Default")
      (node (ref "J4") (pin "14") (pinfunction "14_14") (pintype "passive"))
      (node (ref "U10") (pin "2") (pinfunction "I/O_2") (pintype "passive"))
      (node (ref "U10") (pin "9") (pinfunction "NC_9") (pintype "passive"))
    )
    (net (code "32") (name "/MIPI_CSI1_RX_D2_P") (class "Default")
      (node (ref "J4") (pin "13") (pinfunction "13_13") (pintype "passive"))
      (node (ref "U10") (pin "1") (pinfunction "I/O_1") (pintype "passive"))
      (node (ref "U10") (pin "10") (pinfunction "NC_10") (pintype "passive"))
    )
    (net (code "33") (name "/MIPI_CSI1_RX_D3_N") (class "Default")
      (node (ref "J4") (pin "17") (pinfunction "17_17") (pintype "passive"))
      (node (ref "U10") (pin "5") (pinfunction "I/O_5") (pintype "passive"))
      (node (ref "U10") (pin "6") (pinfunction "NC_6") (pintype "passive"))
    )
    (net (code "34") (name "/MIPI_CSI1_RX_D3_P") (class "Default")
      (node (ref "J4") (pin "16") (pinfunction "16_16") (pintype "passive"))
      (node (ref "U10") (pin "4") (pinfunction "I/O_4") (pintype "passive"))
      (node (ref "U10") (pin "7") (pinfunction "NC_7") (pintype "passive"))
    )
    (net (code "35") (name "/MIPI_CSI_CAM0_CLKOUT") (class "Default")
      (node (ref "J3") (pin "27") (pinfunction "27_27") (pintype "passive"))
      (node (ref "U11") (pin "1") (pinfunction "I/O_1") (pintype "passive"))
      (node (ref "U11") (pin "10") (pinfunction "NC_10") (pintype "passive"))
    )
    (net (code "36") (name "/MIPI_CSI_CAM0_PDN") (class "Default")
      (node (ref "R26") (pin "1") (pinfunction "1_1") (pintype "passive"))
    )
    (net (code "37") (name "/MIPI_CSI_CAM0_RST") (class "Default")
      (node (ref "R28") (pin "1") (pinfunction "1_1") (pintype "passive"))
    )
    (net (code "38") (name "/MIPI_CSI_CAM1_CLKOUT") (class "Default")
      (node (ref "J4") (pin "27") (pinfunction "27_27") (pintype "passive"))
      (node (ref "U12") (pin "1") (pinfunction "I/O_1") (pintype "passive"))
      (node (ref "U12") (pin "10") (pinfunction "NC_10") (pintype "passive"))
    )
    (net (code "39") (name "/MIPI_CSI_CAM1_PDN") (class "Default")
      (node (ref "R27") (pin "1") (pinfunction "1_1") (pintype "passive"))
    )
    (net (code "40") (name "/MIPI_CSI_CAM1_RST") (class "Default")
      (node (ref "R29") (pin "1") (pinfunction "1_1") (pintype "passive"))
    )
    (net (code "41") (name "GND") (class "Default")
      (node (ref "C15") (pin "1") (pinfunction "1_1") (pintype "passive"))
      (node (ref "C16") (pin "1") (pinfunction "1_1") (pintype "passive"))
      (node (ref "C17") (pin "1") (pinfunction "1_1") (pintype "passive"))
      (node (ref "C18") (pin "1") (pinfunction "1_1") (pintype "passive"))
      (node (ref "C19") (pin "1") (pinfunction "1_1") (pintype "passive"))
      (node (ref "C20") (pin "1") (pinfunction "1_1") (pintype "passive"))
      (node (ref "C21") (pin "1") (pinfunction "1_1") (pintype "passive"))
      (node (ref "C22") (pin "1") (pinfunction "1_1") (pintype "passive"))
      (node (ref "C23") (pin "1") (pinfunction "1_1") (pintype "passive"))
      (node (ref "C24") (pin "1") (pinfunction "1_1") (pintype "passive"))
      (node (ref "C25") (pin "1") (pinfunction "1_1") (pintype "passive"))
      (node (ref "C26") (pin "1") (pinfunction "1_1") (pintype "passive"))
      (node (ref "C27") (pin "1") (pinfunction "1_1") (pintype "passive"))
      (node (ref "C28") (pin "1") (pinfunction "1_1") (pintype "passive"))
      (node (ref "C29") (pin "1") (pinfunction "1_1") (pintype "passive"))
      (node (ref "C30") (pin "1") (pinfunction "1_1") (pintype "passive"))
      (node (ref "C31") (pin "1") (pinfunction "1_1") (pintype "passive"))
      (node (ref "C32") (pin "1") (pinfunction "1_1") (pintype "passive"))
      (node (ref "C33") (pin "1") (pinfunction "1_1") (pintype "passive"))
      (node (ref "C34") (pin "1") (pinfunction "1_1") (pintype "passive"))
      (node (ref "C35") (pin "1") (pinfunction "1_1") (pintype "passive"))
      (node (ref "C36") (pin "1") (pinfunction "1_1") (pintype "passive"))
      (node (ref "C37") (pin "1") (pinfunction "1_1") (pintype "passive"))
      (node (ref "C38") (pin "1") (pinfunction "1_1") (pintype "passive"))
      (node (ref "C39") (pin "1") (pinfunction "1_1") (pintype "passive"))
      (node (ref "C40") (pin "1") (pinfunction "1_1") (pintype "passive"))
      (node (ref "C41") (pin "1") (pinfunction "1_1") (pintype "passive"))
      (node (ref "C42") (pin "1") (pinfunction "1_1") (pintype "passive"))
      (node (ref "C43") (pin "1") (pinfunction "1_1") (pintype "passive"))
      (node (ref "C44") (pin "1") (pinfunction "1_1") (pintype "passive"))
      (node (ref "C45") (pin "1") (pinfunction "1_1") (pintype "passive"))
      (node (ref "C46") (pin "1") (pinfunction "1_1") (pintype "passive"))
      (node (ref "C47") (pin "1") (pinfunction "1_1") (pintype "passive"))
      (node (ref "C48") (pin "1") (pinfunction "1_1") (pintype "passive"))
      (node (ref "C49") (pin "1") (pinfunction "1_1") (pintype "passive"))
      (node (ref "C50") (pin "1") (pinfunction "1_1") (pintype "passive"))
      (node (ref "C51") (pin "1") (pinfunction "1_1") (pintype "passive"))
      (node (ref "C52") (pin "1") (pinfunction "1_1") (pintype "passive"))
      (node (ref "D10") (pin "1") (pinfunction "1_1") (pintype "passive"))
      (node (ref "D11") (pin "1") (pinfunction "1_1") (pintype "passive"))
      (node (ref "D12") (pin "1") (pinfunction "1_1") (pintype "passive"))
      (node (ref "D5") (pin "1") (pinfunction "1_1") (pintype "passive"))
      (node (ref "D6") (pin "1") (pinfunction "1_1") (pintype "passive"))
      (node (ref "D7") (pin "1") (pinfunction "1_1") (pintype "passive"))
      (node (ref "D8") (pin "1") (pinfunction "1_1") (pintype "passive"))
      (node (ref "D9") (pin "1") (pinfunction "1_1") (pintype "passive"))
      (node (ref "J3") (pin "12") (pinfunction "12_12") (pintype "passive"))
      (node (ref "J3") (pin "15") (pinfunction "15_15") (pintype "passive"))
      (node (ref "J3") (pin "18") (pinfunction "18_18") (pintype "passive"))
      (node (ref "J3") (pin "26") (pinfunction "26_26") (pintype "passive"))
      (node (ref "J3") (pin "28") (pinfunction "28_28") (pintype "passive"))
      (node (ref "J3") (pin "31") (pinfunction "31_31") (pintype "passive"))
      (node (ref "J3") (pin "34") (pinfunction "34_34") (pintype "passive"))
      (node (ref "J3") (pin "37") (pinfunction "37_37") (pintype "passive"))
      (node (ref "J3") (pin "41") (pinfunction "41_41") (pintype "passive"))
      (node (ref "J3") (pin "42") (pinfunction "42_42") (pintype "passive"))
      (node (ref "J3") (pin "7") (pinfunction "7_7") (pintype "passive"))
      (node (ref "J3") (pin "9") (pinfunction "9_9") (pintype "passive"))
      (node (ref "J4") (pin "12") (pinfunction "12_12") (pintype "passive"))
      (node (ref "J4") (pin "15") (pinfunction "15_15") (pintype "passive"))
      (node (ref "J4") (pin "18") (pinfunction "18_18") (pintype "passive"))
      (node (ref "J4") (pin "26") (pinfunction "26_26") (pintype "passive"))
      (node (ref "J4") (pin "28") (pinfunction "28_28") (pintype "passive"))
      (node (ref "J4") (pin "31") (pinfunction "31_31") (pintype "passive"))
      (node (ref "J4") (pin "34") (pinfunction "34_34") (pintype "passive"))
      (node (ref "J4") (pin "37") (pinfunction "37_37") (pintype "passive"))
      (node (ref "J4") (pin "41") (pinfunction "41_41") (pintype "passive"))
      (node (ref "J4") (pin "42") (pinfunction "42_42") (pintype "passive"))
      (node (ref "J4") (pin "7") (pinfunction "7_7") (pintype "passive"))
      (node (ref "J4") (pin "9") (pinfunction "9_9") (pintype "passive"))
      (node (ref "U10") (pin "3") (pinfunction "GND_3") (pintype "passive"))
      (node (ref "U10") (pin "8") (pinfunction "GND_8") (pintype "passive"))
      (node (ref "U11") (pin "3") (pinfunction "GND_3") (pintype "passive"))
      (node (ref "U11") (pin "8") (pinfunction "GND_8") (pintype "passive"))
      (node (ref "U12") (pin "3") (pinfunction "GND_3") (pintype "passive"))
      (node (ref "U12") (pin "8") (pinfunction "GND_8") (pintype "passive"))
      (node (ref "U13") (pin "3") (pinfunction "GND_3") (pintype "passive"))
      (node (ref "U13") (pin "8") (pinfunction "GND_8") (pintype "passive"))
      (node (ref "U14") (pin "3") (pinfunction "GND_3") (pintype "passive"))
      (node (ref "U14") (pin "8") (pinfunction "GND_8") (pintype "passive"))
      (node (ref "U3") (pin "2") (pinfunction "GND_2") (pintype "passive"))
      (node (ref "U4") (pin "2") (pinfunction "GND_2") (pintype "passive"))
      (node (ref "U5") (pin "2") (pinfunction "GND_2") (pintype "passive"))
      (node (ref "U6") (pin "2") (pinfunction "GND_2") (pintype "passive"))
      (node (ref "U7") (pin "2") (pinfunction "GND_2") (pintype "passive"))
      (node (ref "U8") (pin "2") (pinfunction "GND_2") (pintype "passive"))
      (node (ref "U9") (pin "3") (pinfunction "GND_3") (pintype "passive"))
      (node (ref "U9") (pin "8") (pinfunction "GND_8") (pintype "passive"))
    )
    (net (code "42") (name "Net-(U3-BP)") (class "Default")
      (node (ref "C19") (pin "2") (pinfunction "2_2") (pintype "passive"))
      (node (ref "U3") (pin "4") (pinfunction "BP_4") (pintype "passive"))
    )
    (net (code "43") (name "Net-(U3-EN)") (class "Default")
      (node (ref "C21") (pin "2") (pinfunction "2_2") (pintype "passive"))
      (node (ref "R10") (pin "2") (pinfunction "2_2") (pintype "passive"))
      (node (ref "U3") (pin "3") (pinfunction "EN_3") (pintype "passive"))
    )
    (net (code "44") (name "Net-(U4-BP)") (class "Default")
      (node (ref "C20") (pin "2") (pinfunction "2_2") (pintype "passive"))
      (node (ref "U4") (pin "4") (pinfunction "BP_4") (pintype "passive"))
    )
    (net (code "45") (name "Net-(U4-EN)") (class "Default")
      (node (ref "C22") (pin "2") (pinfunction "2_2") (pintype "passive"))
      (node (ref "R11") (pin "2") (pinfunction "2_2") (pintype "passive"))
      (node (ref "U4") (pin "3") (pinfunction "EN_3") (pintype "passive"))
    )
    (net (code "46") (name "Net-(U5-BP)") (class "Default")
      (node (ref "C27") (pin "2") (pinfunction "2_2") (pintype "passive"))
      (node (ref "U5") (pin "4") (pinfunction "BP_4") (pintype "passive"))
    )
    (net (code "47") (name "Net-(U5-EN)") (class "Default")
      (node (ref "C29") (pin "2") (pinfunction "2_2") (pintype "passive"))
      (node (ref "R12") (pin "2") (pinfunction "2_2") (pintype "passive"))
      (node (ref "U5") (pin "3") (pinfunction "EN_3") (pintype "passive"))
    )
    (net (code "48") (name "Net-(U6-BP)") (class "Default")
      (node (ref "C28") (pin "2") (pinfunction "2_2") (pintype "passive"))
      (node (ref "U6") (pin "4") (pinfunction "BP_4") (pintype "passive"))
    )
    (net (code "49") (name "Net-(U6-EN)") (class "Default")
      (node (ref "C30") (pin "2") (pinfunction "2_2") (pintype "passive"))
      (node (ref "R13") (pin "2") (pinfunction "2_2") (pintype "passive"))
      (node (ref "U6") (pin "3") (pinfunction "EN_3") (pintype "passive"))
    )
    (net (code "50") (name "Net-(U7-BP)") (class "Default")
      (node (ref "C35") (pin "2") (pinfunction "2_2") (pintype "passive"))
      (node (ref "U7") (pin "4") (pinfunction "BP_4") (pintype "passive"))
    )
    (net (code "51") (name "Net-(U7-EN)") (class "Default")
      (node (ref "C37") (pin "2") (pinfunction "2_2") (pintype "passive"))
      (node (ref "R14") (pin "2") (pinfunction "2_2") (pintype "passive"))
      (node (ref "U7") (pin "3") (pinfunction "EN_3") (pintype "passive"))
    )
    (net (code "52") (name "Net-(U8-BP)") (class "Default")
      (node (ref "C36") (pin "2") (pinfunction "2_2") (pintype "passive"))
      (node (ref "U8") (pin "4") (pinfunction "BP_4") (pintype "passive"))
    )
    (net (code "53") (name "Net-(U8-EN)") (class "Default")
      (node (ref "C38") (pin "2") (pinfunction "2_2") (pintype "passive"))
      (node (ref "R15") (pin "2") (pinfunction "2_2") (pintype "passive"))
      (node (ref "U8") (pin "3") (pinfunction "EN_3") (pintype "passive"))
    )
    (net (code "54") (name "VCC_1V2_CAM0") (class "Default")
      (node (ref "C32") (pin "2") (pinfunction "2_2") (pintype "passive"))
      (node (ref "C49") (pin "2") (pinfunction "2_2") (pintype "passive"))
      (node (ref "C50") (pin "2") (pinfunction "2_2") (pintype "passive"))
      (node (ref "J3") (pin "23") (pinfunction "23_23") (pintype "passive"))
      (node (ref "U7") (pin "5") (pinfunction "OUT_5") (pintype "passive"))
    )
    (net (code "55") (name "VCC_1V2_CAM1") (class "Default")
      (node (ref "C34") (pin "2") (pinfunction "2_2") (pintype "passive"))
      (node (ref "C51") (pin "2") (pinfunction "2_2") (pintype "passive"))
      (node (ref "C52") (pin "2") (pinfunction "2_2") (pintype "passive"))
      (node (ref "J4") (pin "23") (pinfunction "23_23") (pintype "passive"))
      (node (ref "U8") (pin "5") (pinfunction "OUT_5") (pintype "passive"))
    )
    (net (code "56") (name "VCC_1V8") (class "Default")
      (node (ref "R16") (pin "2") (pinfunction "2_2") (pintype "passive"))
      (node (ref "R17") (pin "2") (pinfunction "2_2") (pintype "passive"))
      (node (ref "R18") (pin "1") (pinfunction "1_1") (pintype "passive"))
      (node (ref "R20") (pin "1") (pinfunction "1_1") (pintype "passive"))
      (node (ref "R22") (pin "1") (pinfunction "1_1") (pintype "passive"))
      (node (ref "R24") (pin "1") (pinfunction "1_1") (pintype "passive"))
    )
    (net (code "57") (name "VCC_1V8_CAM0") (class "Default")
      (node (ref "C24") (pin "2") (pinfunction "2_2") (pintype "passive"))
      (node (ref "C45") (pin "2") (pinfunction "2_2") (pintype "passive"))
      (node (ref "C46") (pin "2") (pinfunction "2_2") (pintype "passive"))
      (node (ref "J3") (pin "19") (pinfunction "19_19") (pintype "passive"))
      (node (ref "U5") (pin "5") (pinfunction "OUT_5") (pintype "passive"))
    )
    (net (code "58") (name "VCC_1V8_CAM1") (class "Default")
      (node (ref "C26") (pin "2") (pinfunction "2_2") (pintype "passive"))
      (node (ref "C47") (pin "2") (pinfunction "2_2") (pintype "passive"))
      (node (ref "C48") (pin "2") (pinfunction "2_2") (pintype "passive"))
      (node (ref "J4") (pin "19") (pinfunction "19_19") (pintype "passive"))
      (node (ref "U6") (pin "5") (pinfunction "OUT_5") (pintype "passive"))
    )
    (net (code "59") (name "VCC_2V8_CAM0") (class "Default")
      (node (ref "C16") (pin "2") (pinfunction "2_2") (pintype "passive"))
      (node (ref "C41") (pin "2") (pinfunction "2_2") (pintype "passive"))
      (node (ref "C42") (pin "2") (pinfunction "2_2") (pintype "passive"))
      (node (ref "J3") (pin "2") (pinfunction "2_2") (pintype "passive"))
      (node (ref "U3") (pin "5") (pinfunction "OUT_5") (pintype "passive"))
    )
    (net (code "60") (name "VCC_2V8_CAM1") (class "Default")
      (node (ref "C18") (pin "2") (pinfunction "2_2") (pintype "passive"))
      (node (ref "C43") (pin "2") (pinfunction "2_2") (pintype "passive"))
      (node (ref "C44") (pin "2") (pinfunction "2_2") (pintype "passive"))
      (node (ref "J4") (pin "2") (pinfunction "2_2") (pintype "passive"))
      (node (ref "U4") (pin "5") (pinfunction "OUT_5") (pintype "passive"))
    )
    (net (code "61") (name "VCC_3V3") (class "Default")
      (node (ref "C15") (pin "2") (pinfunction "2_2") (pintype "passive"))
      (node (ref "C17") (pin "2") (pinfunction "2_2") (pintype "passive"))
      (node (ref "C23") (pin "2") (pinfunction "2_2") (pintype "passive"))
      (node (ref "C25") (pin "2") (pinfunction "2_2") (pintype "passive"))
      (node (ref "C31") (pin "2") (pinfunction "2_2") (pintype "passive"))
      (node (ref "C33") (pin "2") (pinfunction "2_2") (pintype "passive"))
      (node (ref "U3") (pin "1") (pinfunction "IN_1") (pintype "passive"))
      (node (ref "U4") (pin "1") (pinfunction "IN_1") (pintype "passive"))
      (node (ref "U5") (pin "1") (pinfunction "IN_1") (pintype "passive"))
      (node (ref "U6") (pin "1") (pinfunction "IN_1") (pintype "passive"))
      (node (ref "U7") (pin "1") (pinfunction "IN_1") (pintype "passive"))
      (node (ref "U8") (pin "1") (pinfunction "IN_1") (pintype "passive"))
    )
    (net (code "62") (name "unconnected-(J3-Pad1)") (class "Default")
      (node (ref "J3") (pin "1") (pinfunction "1_1") (pintype "passive+no_connect"))
    )
    (net (code "63") (name "unconnected-(J3-Pad3)") (class "Default")
      (node (ref "J3") (pin "3") (pinfunction "3_3") (pintype "passive+no_connect"))
    )
    (net (code "64") (name "unconnected-(J3-Pad4)") (class "Default")
      (node (ref "J3") (pin "4") (pinfunction "4_4") (pintype "passive+no_connect"))
    )
    (net (code "65") (name "unconnected-(J3-Pad8)") (class "Default")
      (node (ref "J3") (pin "8") (pinfunction "8_8") (pintype "passive+no_connect"))
    )
    (net (code "66") (name "unconnected-(J3-Pad10)") (class "Default")
      (node (ref "J3") (pin "10") (pinfunction "10_10") (pintype "passive+no_connect"))
    )
    (net (code "67") (name "unconnected-(J3-Pad11)") (class "Default")
      (node (ref "J3") (pin "11") (pinfunction "11_11") (pintype "passive+no_connect"))
    )
    (net (code "68") (name "unconnected-(J3-Pad20)") (class "Default")
      (node (ref "J3") (pin "20") (pinfunction "20_20") (pintype "passive+no_connect"))
    )
    (net (code "69") (name "unconnected-(J3-Pad21)") (class "Default")
      (node (ref "J3") (pin "21") (pinfunction "21_21") (pintype "passive+no_connect"))
    )
    (net (code "70") (name "unconnected-(J3-Pad22)") (class "Default")
      (node (ref "J3") (pin "22") (pinfunction "22_22") (pintype "passive+no_connect"))
    )
    (net (code "71") (name "unconnected-(J3-Pad38)") (class "Default")
      (node (ref "J3") (pin "38") (pinfunction "38_38") (pintype "passive+no_connect"))
    )
    (net (code "72") (name "unconnected-(J3-Pad39)") (class "Default")
      (node (ref "J3") (pin "39") (pinfunction "39_39") (pintype "passive+no_connect"))
    )
    (net (code "73") (name "unconnected-(J3-Pad40)") (class "Default")
      (node (ref "J3") (pin "40") (pinfunction "40_40") (pintype "passive+no_connect"))
    )
    (net (code "74") (name "unconnected-(J4-Pad1)") (class "Default")
      (node (ref "J4") (pin "1") (pinfunction "1_1") (pintype "passive+no_connect"))
    )
    (net (code "75") (name "unconnected-(J4-Pad3)") (class "Default")
      (node (ref "J4") (pin "3") (pinfunction "3_3") (pintype "passive+no_connect"))
    )
    (net (code "76") (name "unconnected-(J4-Pad4)") (class "Default")
      (node (ref "J4") (pin "4") (pinfunction "4_4") (pintype "passive+no_connect"))
    )
    (net (code "77") (name "unconnected-(J4-Pad8)") (class "Default")
      (node (ref "J4") (pin "8") (pinfunction "8_8") (pintype "passive+no_connect"))
    )
    (net (code "78") (name "unconnected-(J4-Pad10)") (class "Default")
      (node (ref "J4") (pin "10") (pinfunction "10_10") (pintype "passive+no_connect"))
    )
    (net (code "79") (name "unconnected-(J4-Pad11)") (class "Default")
      (node (ref "J4") (pin "11") (pinfunction "11_11") (pintype "passive+no_connect"))
    )
    (net (code "80") (name "unconnected-(J4-Pad20)") (class "Default")
      (node (ref "J4") (pin "20") (pinfunction "20_20") (pintype "passive+no_connect"))
    )
    (net (code "81") (name "unconnected-(J4-Pad21)") (class "Default")
      (node (ref "J4") (pin "21") (pinfunction "21_21") (pintype "passive+no_connect"))
    )
    (net (code "82") (name "unconnected-(J4-Pad22)") (class "Default")
      (node (ref "J4") (pin "22") (pinfunction "22_22") (pintype "passive+no_connect"))
    )
    (net (code "83") (name "unconnected-(J4-Pad38)") (class "Default")
      (node (ref "J4") (pin "38") (pinfunction "38_38") (pintype "passive+no_connect"))
    )
    (net (code "84") (name "unconnected-(J4-Pad39)") (class "Default")
      (node (ref "J4") (pin "39") (pinfunction "39_39") (pintype "passive+no_connect"))
    )
    (net (code "85") (name "unconnected-(J4-Pad40)") (class "Default")
      (node (ref "J4") (pin "40") (pinfunction "40_40") (pintype "passive+no_connect"))
    )
    (net (code "86") (name "unconnected-(U11-I{slash}O-Pad2)") (class "Default")
      (node (ref "U11") (pin "2") (pinfunction "I/O_2") (pintype "passive+no_connect"))
    )
    (net (code "87") (name "unconnected-(U11-NC-Pad9)") (class "Default")
      (node (ref "U11") (pin "9") (pinfunction "NC_9") (pintype "passive+no_connect"))
    )
    (net (code "88") (name "unconnected-(U12-I{slash}O-Pad2)") (class "Default")
      (node (ref "U12") (pin "2") (pinfunction "I/O_2") (pintype "passive+no_connect"))
    )
    (net (code "89") (name "unconnected-(U12-NC-Pad9)") (class "Default")
      (node (ref "U12") (pin "9") (pinfunction "NC_9") (pintype "passive+no_connect"))
    )
  )
)
